# Minimal_ATTINY2313.net
KiCad netlist of a schematic drawn in EAGLE
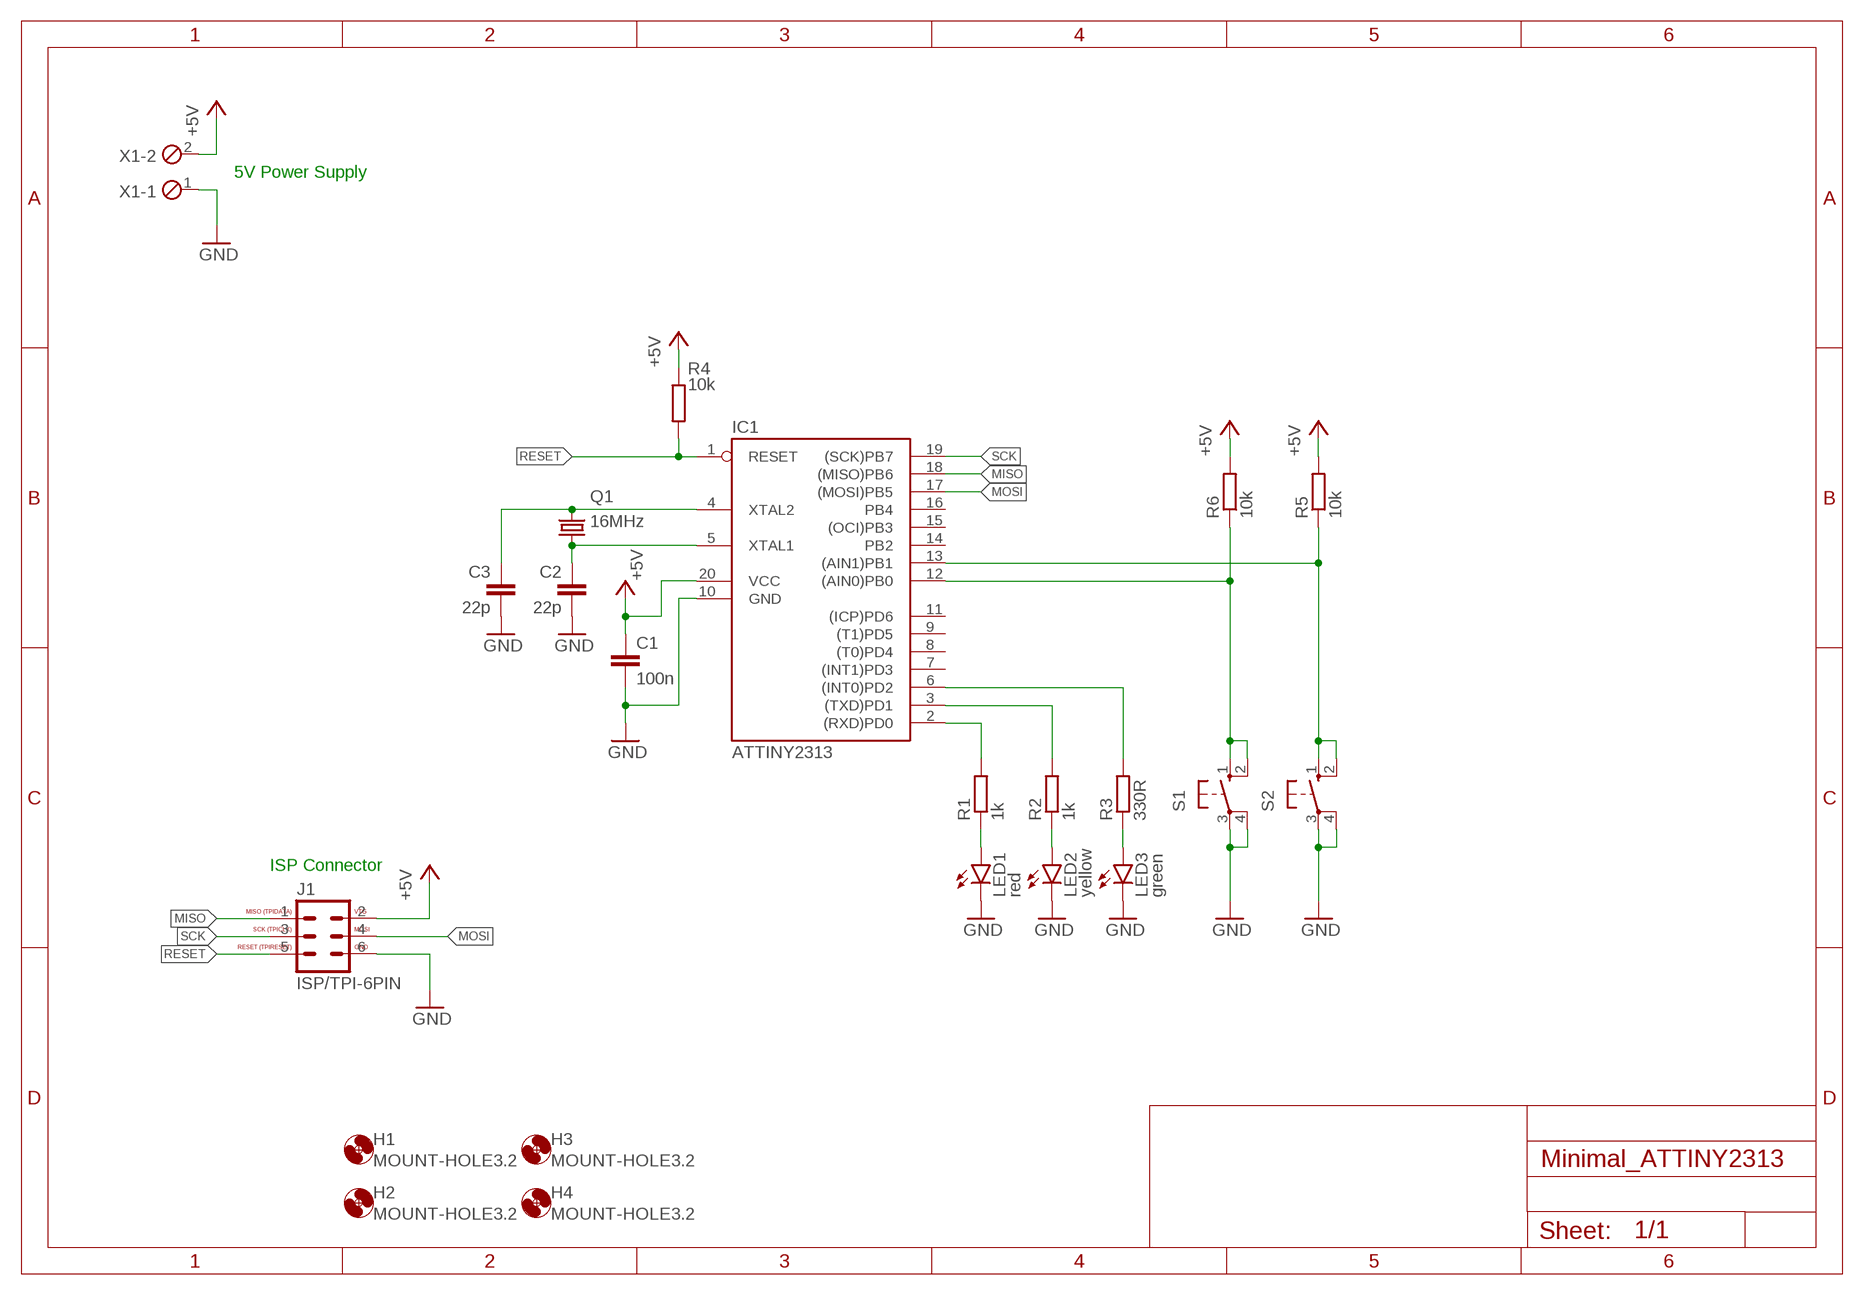
[diagram p0: schematic, sheet 1]

(export (version "E")
  (design (tool "Eeschema 10.0.6"))
  (components
    (comp (ref "C1")
      (value "100n")
      (footprint "eagle-import:C050-024X044")
      (libsource (lib "eagle-import") (part "C-EU050-024X044"))
    )
    (comp (ref "C2")
      (value "22p")
      (footprint "eagle-import:C025-025X050")
      (libsource (lib "eagle-import") (part "C-EU025-025X050"))
    )
    (comp (ref "C3")
      (value "22p")
      (footprint "eagle-import:C025-025X050")
      (libsource (lib "eagle-import") (part "C-EU025-025X050"))
    )
    (comp (ref "H1")
      (value "MOUNT-HOLE3.2")
      (footprint "eagle-import:3,2")
      (libsource (lib "eagle-import") (part "MOUNT-HOLE3.2"))
    )
    (comp (ref "H2")
      (value "MOUNT-HOLE3.2")
      (footprint "eagle-import:3,2")
      (libsource (lib "eagle-import") (part "MOUNT-HOLE3.2"))
    )
    (comp (ref "H3")
      (value "MOUNT-HOLE3.2")
      (footprint "eagle-import:3,2")
      (libsource (lib "eagle-import") (part "MOUNT-HOLE3.2"))
    )
    (comp (ref "H4")
      (value "MOUNT-HOLE3.2")
      (footprint "eagle-import:3,2")
      (libsource (lib "eagle-import") (part "MOUNT-HOLE3.2"))
    )
    (comp (ref "IC1")
      (value "ATTINY2313")
      (footprint "eagle-import:DIL20")
      (libsource (lib "eagle-import") (part "AT90S2313P"))
    )
    (comp (ref "J1")
      (value "ISP/TPI-6PIN")
      (footprint "eagle-import:ML6")
      (libsource (lib "eagle-import") (part "ISP/TPI-6PIN"))
    )
    (comp (ref "LED1")
      (value "red")
      (footprint "eagle-import:LED5MM")
      (libsource (lib "eagle-import") (part "LED5MM"))
    )
    (comp (ref "LED2")
      (value "yellow")
      (footprint "eagle-import:LED5MM")
      (libsource (lib "eagle-import") (part "LED5MM"))
    )
    (comp (ref "LED3")
      (value "green")
      (footprint "eagle-import:LED5MM")
      (libsource (lib "eagle-import") (part "LED5MM"))
    )
    (comp (ref "Q1")
      (value "16MHz")
      (footprint "eagle-import:HC49U-V")
      (libsource (lib "eagle-import") (part "CRYSTALHC49U-V"))
    )
    (comp (ref "R1")
      (value "1k")
      (footprint "eagle-import:0207_5V")
      (libsource (lib "eagle-import") (part "R-EU_0207/5V"))
    )
    (comp (ref "R2")
      (value "1k")
      (footprint "eagle-import:0207_5V")
      (libsource (lib "eagle-import") (part "R-EU_0207/5V"))
    )
    (comp (ref "R3")
      (value "330R")
      (footprint "eagle-import:0207_5V")
      (libsource (lib "eagle-import") (part "R-EU_0207/5V"))
    )
    (comp (ref "R4")
      (value "10k")
      (footprint "eagle-import:0207_5V")
      (libsource (lib "eagle-import") (part "R-EU_0207/5V"))
    )
    (comp (ref "R5")
      (value "10k")
      (footprint "eagle-import:0207_5V")
      (libsource (lib "eagle-import") (part "R-EU_0207/5V"))
    )
    (comp (ref "R6")
      (value "10k")
      (footprint "eagle-import:0207_5V")
      (libsource (lib "eagle-import") (part "R-EU_0207/5V"))
    )
    (comp (ref "S1")
      (value "10-XX")
      (footprint "eagle-import:B3F-10XX")
      (fields (field (name "MPN") "B3F-1000"))
      (libsource (lib "eagle-import") (part "10-XX"))
    )
    (comp (ref "S2")
      (value "10-XX")
      (footprint "eagle-import:B3F-10XX")
      (fields (field (name "MPN") "B3F-1000"))
      (libsource (lib "eagle-import") (part "10-XX"))
    )
    (comp (ref "X1")
      (value "MPT2")
      (footprint "eagle-import:2POL254")
      (libsource (lib "eagle-import") (part "MPT2"))
    )
  )
  (nets
    (net (code "1") (name "+5V") (class "Default")
      (node (ref "C1") (pin "1") (pinfunction "1_1") (pintype "passive"))
      (node (ref "IC1") (pin "20") (pinfunction "VCC_20") (pintype "power_in"))
      (node (ref "J1") (pin "2") (pinfunction "2_2") (pintype "passive"))
      (node (ref "R4") (pin "1") (pinfunction "1_1") (pintype "passive"))
      (node (ref "R5") (pin "2") (pinfunction "2_2") (pintype "passive"))
      (node (ref "R6") (pin "2") (pinfunction "2_2") (pintype "passive"))
      (node (ref "X1") (pin "2") (pinfunction "1_2") (pintype "passive"))
    )
    (net (code "2") (name "GND") (class "Default")
      (node (ref "C1") (pin "2") (pinfunction "2_2") (pintype "passive"))
      (node (ref "C2") (pin "2") (pinfunction "2_2") (pintype "passive"))
      (node (ref "C3") (pin "2") (pinfunction "2_2") (pintype "passive"))
      (node (ref "IC1") (pin "10") (pinfunction "GND_10") (pintype "power_in"))
      (node (ref "J1") (pin "6") (pinfunction "6_6") (pintype "passive"))
      (node (ref "LED1") (pin "K") (pinfunction "C_K") (pintype "passive"))
      (node (ref "LED2") (pin "K") (pinfunction "C_K") (pintype "passive"))
      (node (ref "LED3") (pin "K") (pinfunction "C_K") (pintype "passive"))
      (node (ref "S1") (pin "3") (pinfunction "P_3") (pintype "passive"))
      (node (ref "S1") (pin "4") (pinfunction "P1_4") (pintype "passive"))
      (node (ref "S2") (pin "3") (pinfunction "P_3") (pintype "passive"))
      (node (ref "S2") (pin "4") (pinfunction "P1_4") (pintype "passive"))
      (node (ref "X1") (pin "1") (pinfunction "1_1") (pintype "passive"))
    )
    (net (code "3") (name "MISO") (class "Default")
      (node (ref "IC1") (pin "18") (pinfunction "(MISO)PB6_18") (pintype "bidirectional"))
      (node (ref "J1") (pin "1") (pinfunction "1_1") (pintype "passive"))
    )
    (net (code "4") (name "MOSI") (class "Default")
      (node (ref "IC1") (pin "17") (pinfunction "(MOSI)PB5_17") (pintype "bidirectional"))
      (node (ref "J1") (pin "4") (pinfunction "4_4") (pintype "passive"))
    )
    (net (code "5") (name "Net-(IC1-(AIN0)PB0)") (class "Default")
      (node (ref "IC1") (pin "12") (pinfunction "(AIN0)PB0_12") (pintype "bidirectional"))
      (node (ref "R6") (pin "1") (pinfunction "1_1") (pintype "passive"))
      (node (ref "S1") (pin "1") (pinfunction "S_1") (pintype "passive"))
      (node (ref "S1") (pin "2") (pinfunction "S1_2") (pintype "passive"))
    )
    (net (code "6") (name "Net-(IC1-(AIN1)PB1)") (class "Default")
      (node (ref "IC1") (pin "13") (pinfunction "(AIN1)PB1_13") (pintype "bidirectional"))
      (node (ref "R5") (pin "1") (pinfunction "1_1") (pintype "passive"))
      (node (ref "S2") (pin "1") (pinfunction "S_1") (pintype "passive"))
      (node (ref "S2") (pin "2") (pinfunction "S1_2") (pintype "passive"))
    )
    (net (code "7") (name "Net-(IC1-(INT0)PD2)") (class "Default")
      (node (ref "IC1") (pin "6") (pinfunction "(INT0)PD2_6") (pintype "bidirectional"))
      (node (ref "R3") (pin "2") (pinfunction "2_2") (pintype "passive"))
    )
    (net (code "8") (name "Net-(IC1-(RXD)PD0)") (class "Default")
      (node (ref "IC1") (pin "2") (pinfunction "(RXD)PD0_2") (pintype "bidirectional"))
      (node (ref "R1") (pin "2") (pinfunction "2_2") (pintype "passive"))
    )
    (net (code "9") (name "Net-(IC1-(TXD)PD1)") (class "Default")
      (node (ref "IC1") (pin "3") (pinfunction "(TXD)PD1_3") (pintype "bidirectional"))
      (node (ref "R2") (pin "2") (pinfunction "2_2") (pintype "passive"))
    )
    (net (code "10") (name "Net-(IC1-XTAL1)") (class "Default")
      (node (ref "C2") (pin "1") (pinfunction "1_1") (pintype "passive"))
      (node (ref "IC1") (pin "5") (pinfunction "XTAL1_5") (pintype "bidirectional"))
      (node (ref "Q1") (pin "1") (pinfunction "1_1") (pintype "passive"))
    )
    (net (code "11") (name "Net-(IC1-XTAL2)") (class "Default")
      (node (ref "C3") (pin "1") (pinfunction "1_1") (pintype "passive"))
      (node (ref "IC1") (pin "4") (pinfunction "XTAL2_4") (pintype "bidirectional"))
      (node (ref "Q1") (pin "2") (pinfunction "2_2") (pintype "passive"))
    )
    (net (code "12") (name "Net-(LED1-PadA)") (class "Default")
      (node (ref "LED1") (pin "A") (pinfunction "A_A") (pintype "passive"))
      (node (ref "R1") (pin "1") (pinfunction "1_1") (pintype "passive"))
    )
    (net (code "13") (name "Net-(LED2-PadA)") (class "Default")
      (node (ref "LED2") (pin "A") (pinfunction "A_A") (pintype "passive"))
      (node (ref "R2") (pin "1") (pinfunction "1_1") (pintype "passive"))
    )
    (net (code "14") (name "Net-(LED3-PadA)") (class "Default")
      (node (ref "LED3") (pin "A") (pinfunction "A_A") (pintype "passive"))
      (node (ref "R3") (pin "1") (pinfunction "1_1") (pintype "passive"))
    )
    (net (code "15") (name "RESET") (class "Default")
      (node (ref "IC1") (pin "1") (pinfunction "RESET_1") (pintype "bidirectional"))
      (node (ref "J1") (pin "5") (pinfunction "5_5") (pintype "passive"))
      (node (ref "R4") (pin "2") (pinfunction "2_2") (pintype "passive"))
    )
    (net (code "16") (name "SCK") (class "Default")
      (node (ref "IC1") (pin "19") (pinfunction "(SCK)PB7_19") (pintype "bidirectional"))
      (node (ref "J1") (pin "3") (pinfunction "3_3") (pintype "passive"))
    )
    (net (code "17") (name "unconnected-(IC1-(ICP)PD6-Pad11)") (class "Default")
      (node (ref "IC1") (pin "11") (pinfunction "(ICP)PD6_11") (pintype "bidirectional"))
    )
    (net (code "18") (name "unconnected-(IC1-(INT1)PD3-Pad7)") (class "Default")
      (node (ref "IC1") (pin "7") (pinfunction "(INT1)PD3_7") (pintype "bidirectional"))
    )
    (net (code "19") (name "unconnected-(IC1-(OCI)PB3-Pad15)") (class "Default")
      (node (ref "IC1") (pin "15") (pinfunction "(OCI)PB3_15") (pintype "bidirectional"))
    )
    (net (code "20") (name "unconnected-(IC1-(T0)PD4-Pad8)") (class "Default")
      (node (ref "IC1") (pin "8") (pinfunction "(T0)PD4_8") (pintype "bidirectional"))
    )
    (net (code "21") (name "unconnected-(IC1-(T1)PD5-Pad9)") (class "Default")
      (node (ref "IC1") (pin "9") (pinfunction "(T1)PD5_9") (pintype "bidirectional"))
    )
    (net (code "22") (name "unconnected-(IC1-PB2-Pad14)") (class "Default")
      (node (ref "IC1") (pin "14") (pinfunction "PB2_14") (pintype "bidirectional"))
    )
    (net (code "23") (name "unconnected-(IC1-PB4-Pad16)") (class "Default")
      (node (ref "IC1") (pin "16") (pinfunction "PB4_16") (pintype "bidirectional"))
    )
  )
)
